# Connector.net
KiCad netlist of a schematic drawn in Altium Designer
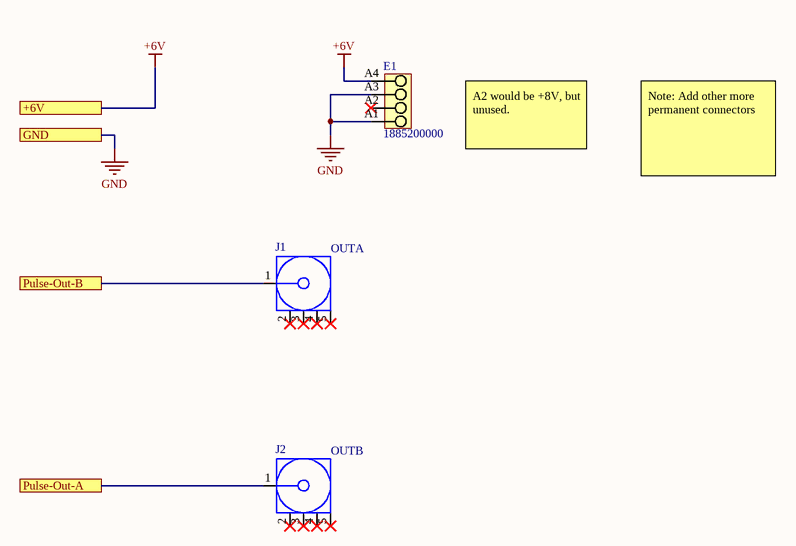
[diagram p0: Connector.SchDoc]

(export (version "E")
  (design (tool "Eeschema 10.0.6"))
  (components
    (comp (ref "E1")
      (value "1885200000")
      (footprint "LSF_SMT_3_5_135_04")
      (description "OMNIMATE Signal - series LSF")
      (fields (field (name "MANUFACTURER") "Weidmueller"))
      (libsource (lib "Altium Content Vault") (part "Terminal_04_1x04"))
    )
    (comp (ref "J1")
      (value "OUTA")
      (footprint "MOLX-731000114_V")
      (description "SMA Right-Angle PCB Jack Receptacle, Brass Body, Gold Plated, 50 Ohm, 5-Pin THD, RoHS, Tray")
      (fields (field (name "MANUFACTURER") "Molex"))
      (libsource (lib "Altium Content Vault") (part "CN-S-4F-RF5"))
    )
    (comp (ref "J2")
      (value "OUTB")
      (footprint "MOLX-731000114_V")
      (description "SMA Right-Angle PCB Jack Receptacle, Brass Body, Gold Plated, 50 Ohm, 5-Pin THD, RoHS, Tray")
      (fields (field (name "MANUFACTURER") "Molex"))
      (libsource (lib "Altium Content Vault") (part "CN-S-4F-RF5"))
    )
  )
  (nets
    (net (code "1") (name "+6V") (class "Default")
      (node (ref "E1") (pin "A4") (pinfunction "A4_A4") (pintype "passive"))
    )
    (net (code "2") (name "/Pulse-Out-A") (class "Default")
      (node (ref "J2") (pin "1") (pinfunction "1_1") (pintype "passive"))
    )
    (net (code "3") (name "/Pulse-Out-B") (class "Default")
      (node (ref "J1") (pin "1") (pinfunction "1_1") (pintype "passive"))
    )
    (net (code "4") (name "GND") (class "Default")
      (node (ref "E1") (pin "A1") (pinfunction "A1_A1") (pintype "passive"))
      (node (ref "E1") (pin "A3") (pinfunction "A3_A3") (pintype "passive"))
    )
    (net (code "5") (name "unconnected-(E1-PadA2)") (class "Default")
      (node (ref "E1") (pin "A2") (pinfunction "A2_A2") (pintype "passive+no_connect"))
    )
    (net (code "6") (name "unconnected-(J1-Pad2)") (class "Default")
      (node (ref "J1") (pin "2") (pinfunction "2_2") (pintype "passive+no_connect"))
    )
    (net (code "7") (name "unconnected-(J1-Pad3)") (class "Default")
      (node (ref "J1") (pin "3") (pinfunction "3_3") (pintype "passive+no_connect"))
    )
    (net (code "8") (name "unconnected-(J1-Pad4)") (class "Default")
      (node (ref "J1") (pin "4") (pinfunction "4_4") (pintype "passive+no_connect"))
    )
    (net (code "9") (name "unconnected-(J1-Pad5)") (class "Default")
      (node (ref "J1") (pin "5") (pinfunction "5_5") (pintype "passive+no_connect"))
    )
    (net (code "10") (name "unconnected-(J2-Pad2)") (class "Default")
      (node (ref "J2") (pin "2") (pinfunction "2_2") (pintype "passive+no_connect"))
    )
    (net (code "11") (name "unconnected-(J2-Pad3)") (class "Default")
      (node (ref "J2") (pin "3") (pinfunction "3_3") (pintype "passive+no_connect"))
    )
    (net (code "12") (name "unconnected-(J2-Pad4)") (class "Default")
      (node (ref "J2") (pin "4") (pinfunction "4_4") (pintype "passive+no_connect"))
    )
    (net (code "13") (name "unconnected-(J2-Pad5)") (class "Default")
      (node (ref "J2") (pin "5") (pinfunction "5_5") (pintype "passive+no_connect"))
    )
  )
)
